# MCU.net
KiCad netlist of a schematic drawn in Altium Designer
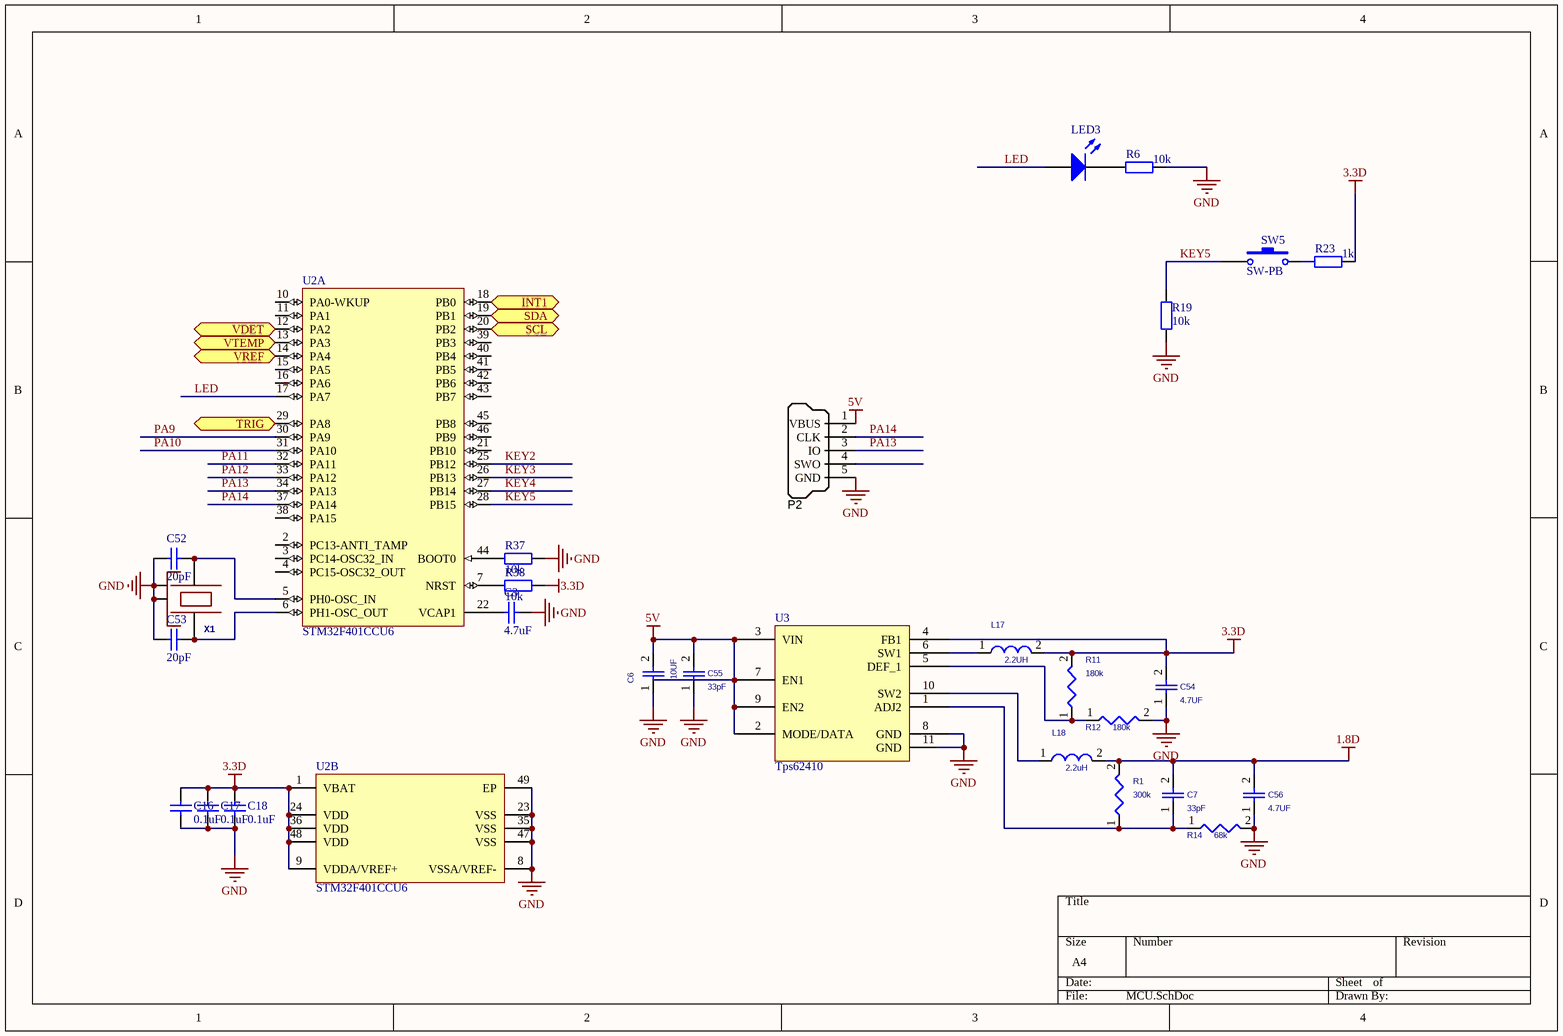
[diagram p0: MCU.SchDoc]

(export (version "E")
  (design (tool "Eeschema 10.0.6"))
  (components
    (comp (ref "C3")
      (value "4.7uF")
      (footprint "0603")
      (description "Capacitor")
      (fields (field (name "Comment") "Cap") (field (name "PUBLISHER") "Altium Limited"))
      (libsource (lib "RTC6705") (part "Cap"))
    )
    (comp (ref "C6") (value "10UF") (footprint "0805") (libsource (lib "*") (part "CAP/0402")))
    (comp (ref "C7") (value "33pF") (footprint "0402") (libsource (lib "*") (part "CAP/0402")))
    (comp (ref "C16")
      (value "0.1uF")
      (footprint "0402")
      (description "Capacitor")
      (fields (field (name "Comment") "Cap") (field (name "PUBLISHER") "Altium Limited"))
      (libsource (lib "RTC6705") (part "Cap"))
    )
    (comp (ref "C17")
      (value "0.1uF")
      (footprint "0402")
      (description "Capacitor")
      (fields (field (name "Comment") "Cap") (field (name "PUBLISHER") "Altium Limited"))
      (libsource (lib "RTC6705") (part "Cap"))
    )
    (comp (ref "C18")
      (value "0.1uF")
      (footprint "0402")
      (description "Capacitor")
      (fields (field (name "Comment") "Cap") (field (name "PUBLISHER") "Altium Limited"))
      (libsource (lib "RTC6705") (part "Cap"))
    )
    (comp (ref "C52")
      (value "20pF")
      (footprint "0402")
      (description "Capacitor")
      (fields (field (name "Comment") "Cap") (field (name "PUBLISHER") "Altium Limited"))
      (libsource (lib "RTC6705") (part "Cap"))
    )
    (comp (ref "C53")
      (value "20pF")
      (footprint "0402")
      (description "Capacitor")
      (fields (field (name "Comment") "Cap") (field (name "PUBLISHER") "Altium Limited"))
      (libsource (lib "RTC6705") (part "Cap"))
    )
    (comp (ref "C54") (value "4.7UF") (footprint "0805") (libsource (lib "*") (part "CAP/0402")))
    (comp (ref "C55") (value "33pF") (footprint "0603L") (libsource (lib "*") (part "CAP/0402")))
    (comp (ref "C56") (value "4.7UF") (footprint "0805") (libsource (lib "*") (part "CAP/0402")))
    (comp (ref "L17") (value "2.2UH") (footprint "0806") (libsource (lib "*") (part "L/2.5*2.0")))
    (comp (ref "L18") (value "2.2uH") (footprint "0806") (libsource (lib "*") (part "L/2.5*2.0")))
    (comp (ref "LED3")
      (value "LED0")
      (footprint "0603")
      (description "Typical INFRARED GaAs LED")
      (fields (field (name "PUBLISHER") "Altium Limited"))
      (libsource (lib "Miscellaneous Devices") (part "LED0"))
    )
    (comp (ref "P2")
      (value "SWD_MicroUSB")
      (footprint "MICRO-YZX")
      (description "Connector SMD USB Micro Type B middle mount")
      (libsource (lib "sch") (part "SWD_MicroUSB"))
    )
    (comp (ref "R1") (value "300k") (footprint "0402") (libsource (lib "*") (part "RES/0402_3")))
    (comp (ref "R6")
      (value "10k")
      (footprint "0402")
      (description "Resistor")
      (fields (field (name "PUBLISHER") "Altium Limited"))
      (libsource (lib "Miscellaneous Devices") (part "Res2"))
    )
    (comp (ref "R11") (value "180k") (footprint "0402") (libsource (lib "*") (part "RES/0402_3")))
    (comp (ref "R12") (value "180k") (footprint "0402") (libsource (lib "*") (part "RES/0402_3")))
    (comp (ref "R14") (value "68k") (footprint "0402") (libsource (lib "*") (part "RES/0402_3")))
    (comp (ref "R19")
      (value "10k")
      (footprint "0402")
      (description "Resistor")
      (fields (field (name "PUBLISHER") "Altium Limited"))
      (libsource (lib "") (part "Res2_1"))
    )
    (comp (ref "R23")
      (value "1k")
      (footprint "0402")
      (description "Resistor")
      (fields (field (name "PUBLISHER") "Altium Limited"))
      (libsource (lib "Miscellaneous Devices") (part "Res2"))
    )
    (comp (ref "R37")
      (value "10k")
      (footprint "0402")
      (description "Resistor")
      (fields (field (name "Comment") "Res2") (field (name "PUBLISHER") "Altium Limited"))
      (libsource (lib "") (part "Res2_1"))
    )
    (comp (ref "R38")
      (value "10k")
      (footprint "0402")
      (description "Resistor")
      (fields (field (name "Comment") "Res2") (field (name "PUBLISHER") "Altium Limited"))
      (libsource (lib "RTC6705") (part "Res2"))
    )
    (comp (ref "SW5")
      (value "SW-PB")
      (footprint "SW3x4")
      (description "Switch")
      (fields (field (name "PUBLISHER") "Altium Limited"))
      (libsource (lib "Miscellaneous Devices") (part "SW-PB"))
    )
    (comp (ref "U2")
      (value "STM32F401CCU6")
      (footprint "STM-UFQFPN48_N")
      (fields (field (name "MANUFACTURER") "STMicroelectronics"))
      (libsource (lib "STMicroelectronics STM32 F4") (part "STM32F401CCU6"))
    )
    (comp (ref "U3") (value "Tps62410") (footprint "DFN-10P-3X3") (libsource (lib "Euler") (part "Tps62410")))
    (comp (ref "X1")
      (value "24.000 KHz 3.2x2.5mm 8-10pf")
      (footprint "OSCILLATOR-3.2X2.5")
      (description "Crystal Oscillator in 3.2x2.5 SMD")
      (libsource (lib "pixhawk2") (part "OSCILLATOR-3.2X2.5"))
    )
  )
  (nets
    (net (code "1") (name "/INT1") (class "Default")
      (node (ref "U2") (pin "18") (pinfunction "PB0_18") (pintype "bidirectional"))
    )
    (net (code "2") (name "/KEY2") (class "Default")
      (node (ref "U2") (pin "25") (pinfunction "PB12_25") (pintype "bidirectional"))
    )
    (net (code "3") (name "/KEY3") (class "Default")
      (node (ref "U2") (pin "26") (pinfunction "PB13_26") (pintype "bidirectional"))
    )
    (net (code "4") (name "/KEY4") (class "Default")
      (node (ref "U2") (pin "27") (pinfunction "PB14_27") (pintype "bidirectional"))
    )
    (net (code "5") (name "/KEY5") (class "Default")
      (node (ref "R19") (pin "2") (pinfunction "2_2") (pintype "passive"))
      (node (ref "SW5") (pin "1") (pinfunction "1_1") (pintype "passive"))
      (node (ref "U2") (pin "28") (pinfunction "PB15_28") (pintype "bidirectional"))
    )
    (net (code "6") (name "/LED") (class "Default")
      (node (ref "LED3") (pin "1") (pinfunction "A_1") (pintype "passive"))
      (node (ref "U2") (pin "17") (pinfunction "PA7_17") (pintype "bidirectional"))
    )
    (net (code "7") (name "/PA9") (class "Default")
      (node (ref "U2") (pin "30") (pinfunction "PA9_30") (pintype "bidirectional"))
    )
    (net (code "8") (name "/PA10") (class "Default")
      (node (ref "U2") (pin "31") (pinfunction "PA10_31") (pintype "bidirectional"))
    )
    (net (code "9") (name "/PA11") (class "Default")
      (node (ref "U2") (pin "32") (pinfunction "PA11_32") (pintype "bidirectional"))
    )
    (net (code "10") (name "/PA12") (class "Default")
      (node (ref "U2") (pin "33") (pinfunction "PA12_33") (pintype "bidirectional"))
    )
    (net (code "11") (name "/PA13") (class "Default")
      (node (ref "P2") (pin "3") (pinfunction "IO_3") (pintype "passive"))
      (node (ref "U2") (pin "34") (pinfunction "PA13_34") (pintype "bidirectional"))
    )
    (net (code "12") (name "/PA14") (class "Default")
      (node (ref "P2") (pin "2") (pinfunction "CLK_2") (pintype "passive"))
      (node (ref "U2") (pin "37") (pinfunction "PA14_37") (pintype "bidirectional"))
    )
    (net (code "13") (name "/SCL") (class "Default")
      (node (ref "U2") (pin "20") (pinfunction "PB2_20") (pintype "bidirectional"))
    )
    (net (code "14") (name "/SDA") (class "Default")
      (node (ref "U2") (pin "19") (pinfunction "PB1_19") (pintype "bidirectional"))
    )
    (net (code "15") (name "/TRIG") (class "Default")
      (node (ref "U2") (pin "29") (pinfunction "PA8_29") (pintype "bidirectional"))
    )
    (net (code "16") (name "/VDET") (class "Default")
      (node (ref "U2") (pin "12") (pinfunction "PA2_12") (pintype "bidirectional"))
    )
    (net (code "17") (name "/VREF") (class "Default")
      (node (ref "U2") (pin "14") (pinfunction "PA4_14") (pintype "bidirectional"))
    )
    (net (code "18") (name "/VTEMP") (class "Default")
      (node (ref "U2") (pin "13") (pinfunction "PA3_13") (pintype "bidirectional"))
    )
    (net (code "19") (name "1.8D") (class "Default")
      (node (ref "C56") (pin "2") (pinfunction "2_2") (pintype "passive"))
      (node (ref "C7") (pin "2") (pinfunction "2_2") (pintype "passive"))
      (node (ref "L18") (pin "2") (pinfunction "2_2") (pintype "passive"))
      (node (ref "R1") (pin "2") (pinfunction "2_2") (pintype "passive"))
    )
    (net (code "20") (name "3.3D") (class "Default")
      (node (ref "C16") (pin "2") (pinfunction "2_2") (pintype "passive"))
      (node (ref "C17") (pin "2") (pinfunction "2_2") (pintype "passive"))
      (node (ref "C18") (pin "2") (pinfunction "2_2") (pintype "passive"))
      (node (ref "C54") (pin "2") (pinfunction "2_2") (pintype "passive"))
      (node (ref "L17") (pin "2") (pinfunction "2_2") (pintype "passive"))
      (node (ref "R11") (pin "2") (pinfunction "2_2") (pintype "passive"))
      (node (ref "R23") (pin "2") (pinfunction "2_2") (pintype "passive"))
      (node (ref "R38") (pin "1") (pinfunction "1_1") (pintype "passive"))
      (node (ref "U2") (pin "1") (pinfunction "VBAT_1") (pintype "power_in"))
      (node (ref "U2") (pin "24") (pinfunction "VDD_24") (pintype "power_in"))
      (node (ref "U2") (pin "36") (pinfunction "VDD_36") (pintype "power_in"))
      (node (ref "U2") (pin "48") (pinfunction "VDD_48") (pintype "power_in"))
      (node (ref "U2") (pin "9") (pinfunction "VDDA/VREF+_9") (pintype "power_in"))
      (node (ref "U3") (pin "4") (pinfunction "FB1_4") (pintype "passive"))
    )
    (net (code "21") (name "5V") (class "Default")
      (node (ref "C55") (pin "2") (pinfunction "2_2") (pintype "passive"))
      (node (ref "C6") (pin "2") (pinfunction "2_2") (pintype "passive"))
      (node (ref "P2") (pin "1") (pinfunction "VBUS_1") (pintype "passive"))
      (node (ref "U3") (pin "2") (pinfunction "MODE/DATA_2") (pintype "passive"))
      (node (ref "U3") (pin "3") (pinfunction "VIN_3") (pintype "passive"))
      (node (ref "U3") (pin "7") (pinfunction "EN1_7") (pintype "passive"))
      (node (ref "U3") (pin "9") (pinfunction "EN2_9") (pintype "passive"))
    )
    (net (code "22") (name "GND") (class "Default")
      (node (ref "C16") (pin "1") (pinfunction "1_1") (pintype "passive"))
      (node (ref "C17") (pin "1") (pinfunction "1_1") (pintype "passive"))
      (node (ref "C18") (pin "1") (pinfunction "1_1") (pintype "passive"))
      (node (ref "C3") (pin "1") (pinfunction "1_1") (pintype "passive"))
      (node (ref "C52") (pin "1") (pinfunction "1_1") (pintype "passive"))
      (node (ref "C53") (pin "1") (pinfunction "1_1") (pintype "passive"))
      (node (ref "C54") (pin "1") (pinfunction "1_1") (pintype "passive"))
      (node (ref "C55") (pin "1") (pinfunction "1_1") (pintype "passive"))
      (node (ref "C56") (pin "1") (pinfunction "1_1") (pintype "passive"))
      (node (ref "C6") (pin "1") (pinfunction "1_1") (pintype "passive"))
      (node (ref "P2") (pin "5") (pinfunction "GND_5") (pintype "passive"))
      (node (ref "R12") (pin "2") (pinfunction "2_2") (pintype "passive"))
      (node (ref "R14") (pin "2") (pinfunction "2_2") (pintype "passive"))
      (node (ref "R19") (pin "1") (pinfunction "1_1") (pintype "passive"))
      (node (ref "R37") (pin "2") (pinfunction "2_2") (pintype "passive"))
      (node (ref "R6") (pin "2") (pinfunction "2_2") (pintype "passive"))
      (node (ref "U2") (pin "23") (pinfunction "VSS_23") (pintype "power_in"))
      (node (ref "U2") (pin "35") (pinfunction "VSS_35") (pintype "power_in"))
      (node (ref "U2") (pin "47") (pinfunction "VSS_47") (pintype "power_in"))
      (node (ref "U2") (pin "49") (pinfunction "EP_49") (pintype "power_in"))
      (node (ref "U2") (pin "8") (pinfunction "VSSA/VREF-_8") (pintype "power_in"))
      (node (ref "U3") (pin "11") (pinfunction "GND_11") (pintype "passive"))
      (node (ref "U3") (pin "8") (pinfunction "GND_8") (pintype "passive"))
      (node (ref "X1") (pin "2") (pinfunction "NC_2_2") (pintype "open_emitter"))
      (node (ref "X1") (pin "4") (pinfunction "NC_4_4") (pintype "open_emitter"))
    )
    (net (code "23") (name "Net-(LED3-K)") (class "Default")
      (node (ref "LED3") (pin "2") (pinfunction "K_2") (pintype "passive"))
      (node (ref "R6") (pin "1") (pinfunction "1_1") (pintype "passive"))
    )
    (net (code "24") (name "Net-(R23-Pad1)") (class "Default")
      (node (ref "R23") (pin "1") (pinfunction "1_1") (pintype "passive"))
      (node (ref "SW5") (pin "2") (pinfunction "2_2") (pintype "passive"))
    )
    (net (code "25") (name "Net-(U2A-BOOT0)") (class "Default")
      (node (ref "R37") (pin "1") (pinfunction "1_1") (pintype "passive"))
      (node (ref "U2") (pin "44") (pinfunction "BOOT0_44") (pintype "input"))
    )
    (net (code "26") (name "Net-(U2A-NRST)") (class "Default")
      (node (ref "R38") (pin "2") (pinfunction "2_2") (pintype "passive"))
      (node (ref "U2") (pin "7") (pinfunction "NRST_7") (pintype "bidirectional"))
    )
    (net (code "27") (name "Net-(U2A-PH0-OSC_IN)") (class "Default")
      (node (ref "C52") (pin "2") (pinfunction "2_2") (pintype "passive"))
      (node (ref "U2") (pin "5") (pinfunction "PH0-OSC_IN_5") (pintype "bidirectional"))
      (node (ref "X1") (pin "1") (pinfunction "1_1") (pintype "passive"))
    )
    (net (code "28") (name "Net-(U2A-PH1-OSC_OUT)") (class "Default")
      (node (ref "C53") (pin "2") (pinfunction "2_2") (pintype "passive"))
      (node (ref "U2") (pin "6") (pinfunction "PH1-OSC_OUT_6") (pintype "bidirectional"))
      (node (ref "X1") (pin "3") (pinfunction "3_3") (pintype "passive"))
    )
    (net (code "29") (name "Net-(U2A-VCAP1)") (class "Default")
      (node (ref "C3") (pin "2") (pinfunction "2_2") (pintype "passive"))
      (node (ref "U2") (pin "22") (pinfunction "VCAP1_22") (pintype "power_in"))
    )
    (net (code "30") (name "Net-(U3-ADJ2)") (class "Default")
      (node (ref "C7") (pin "1") (pinfunction "1_1") (pintype "passive"))
      (node (ref "R1") (pin "1") (pinfunction "1_1") (pintype "passive"))
      (node (ref "R14") (pin "1") (pinfunction "1_1") (pintype "passive"))
      (node (ref "U3") (pin "1") (pinfunction "ADJ2_1") (pintype "passive"))
    )
    (net (code "31") (name "Net-(U3-DEF_1)") (class "Default")
      (node (ref "R11") (pin "1") (pinfunction "1_1") (pintype "passive"))
      (node (ref "R12") (pin "1") (pinfunction "1_1") (pintype "passive"))
      (node (ref "U3") (pin "5") (pinfunction "DEF_1_5") (pintype "passive"))
    )
    (net (code "32") (name "Net-(U3-SW1)") (class "Default")
      (node (ref "L17") (pin "1") (pinfunction "1_1") (pintype "passive"))
      (node (ref "U3") (pin "6") (pinfunction "SW1_6") (pintype "passive"))
    )
    (net (code "33") (name "Net-(U3-SW2)") (class "Default")
      (node (ref "L18") (pin "1") (pinfunction "1_1") (pintype "passive"))
      (node (ref "U3") (pin "10") (pinfunction "SW2_10") (pintype "passive"))
    )
    (net (code "34") (name "unconnected-(P2-SWO-Pad4)") (class "Default")
      (node (ref "P2") (pin "4") (pinfunction "SWO_4") (pintype "passive"))
    )
    (net (code "35") (name "unconnected-(U2A-PA0-WKUP-Pad10)") (class "Default")
      (node (ref "U2") (pin "10") (pinfunction "PA0-WKUP_10") (pintype "bidirectional"))
    )
    (net (code "36") (name "unconnected-(U2A-PA1-Pad11)") (class "Default")
      (node (ref "U2") (pin "11") (pinfunction "PA1_11") (pintype "bidirectional"))
    )
    (net (code "37") (name "unconnected-(U2A-PA5-Pad15)") (class "Default")
      (node (ref "U2") (pin "15") (pinfunction "PA5_15") (pintype "bidirectional"))
    )
    (net (code "38") (name "unconnected-(U2A-PA6-Pad16)") (class "Default")
      (node (ref "U2") (pin "16") (pinfunction "PA6_16") (pintype "bidirectional"))
    )
    (net (code "39") (name "unconnected-(U2A-PA15-Pad38)") (class "Default")
      (node (ref "U2") (pin "38") (pinfunction "PA15_38") (pintype "bidirectional"))
    )
    (net (code "40") (name "unconnected-(U2A-PB3-Pad39)") (class "Default")
      (node (ref "U2") (pin "39") (pinfunction "PB3_39") (pintype "bidirectional"))
    )
    (net (code "41") (name "unconnected-(U2A-PB4-Pad40)") (class "Default")
      (node (ref "U2") (pin "40") (pinfunction "PB4_40") (pintype "bidirectional"))
    )
    (net (code "42") (name "unconnected-(U2A-PB5-Pad41)") (class "Default")
      (node (ref "U2") (pin "41") (pinfunction "PB5_41") (pintype "bidirectional"))
    )
    (net (code "43") (name "unconnected-(U2A-PB6-Pad42)") (class "Default")
      (node (ref "U2") (pin "42") (pinfunction "PB6_42") (pintype "bidirectional"))
    )
    (net (code "44") (name "unconnected-(U2A-PB7-Pad43)") (class "Default")
      (node (ref "U2") (pin "43") (pinfunction "PB7_43") (pintype "bidirectional"))
    )
    (net (code "45") (name "unconnected-(U2A-PB8-Pad45)") (class "Default")
      (node (ref "U2") (pin "45") (pinfunction "PB8_45") (pintype "bidirectional"))
    )
    (net (code "46") (name "unconnected-(U2A-PB9-Pad46)") (class "Default")
      (node (ref "U2") (pin "46") (pinfunction "PB9_46") (pintype "bidirectional"))
    )
    (net (code "47") (name "unconnected-(U2A-PB10-Pad21)") (class "Default")
      (node (ref "U2") (pin "21") (pinfunction "PB10_21") (pintype "bidirectional"))
    )
    (net (code "48") (name "unconnected-(U2A-PC13-ANTI_TAMP-Pad2)") (class "Default")
      (node (ref "U2") (pin "2") (pinfunction "PC13-ANTI_TAMP_2") (pintype "bidirectional"))
    )
    (net (code "49") (name "unconnected-(U2A-PC14-OSC32_IN-Pad3)") (class "Default")
      (node (ref "U2") (pin "3") (pinfunction "PC14-OSC32_IN_3") (pintype "bidirectional"))
    )
    (net (code "50") (name "unconnected-(U2A-PC15-OSC32_OUT-Pad4)") (class "Default")
      (node (ref "U2") (pin "4") (pinfunction "PC15-OSC32_OUT_4") (pintype "bidirectional"))
    )
  )
)
